# 5VBulkhead.net
KiCad netlist of a schematic drawn in Altium Designer
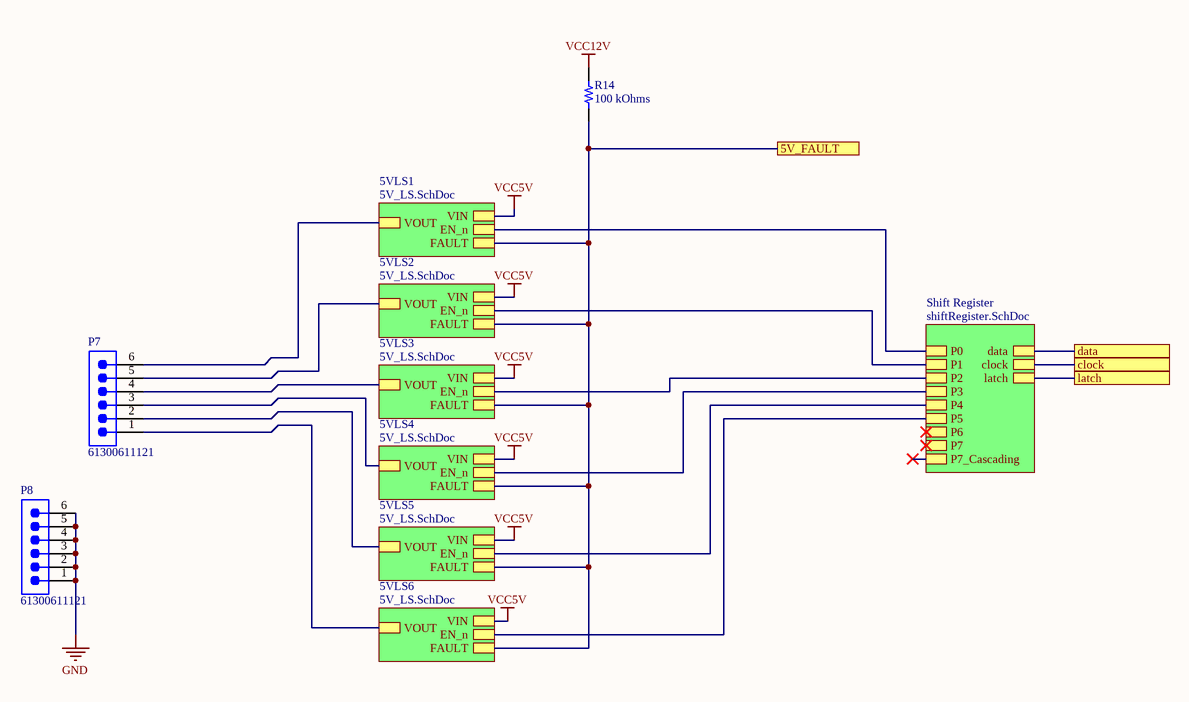
[diagram p0: 5VBulkhead.SchDoc]

(export (version "E")
  (design (tool "Eeschema 10.0.6"))
  (components
    (comp (ref "P7")
      (value "61300611121")
      (footprint "61300611121")
      (libsource (lib "Altium Content Vault") (part "Header_Male_1R_06P"))
    )
    (comp (ref "P8")
      (value "61300611121")
      (footprint "61300611121")
      (libsource (lib "Altium Content Vault") (part "Header_Male_1R_06P"))
    )
    (comp (ref "R14")
      (value "100 kOhms")
      (footprint "RES 0603_1608")
      (description "RES 100K OHM 0.1% 1/16W 0603")
      (fields
        (field (name "PART NUMBER") "RNCS0603BKE100K")
        (field (name "MANUFACTURER") "Stackpole Electronics Inc")
      )
      (libsource (lib "Celestial Altium Library - altium_library") (part "Resistor"))
    )
  )
  (nets
    (net (code "1") (name "/5V_FAULT") (class "Default")
      (node (ref "R14") (pin "1") (pinfunction "1_1") (pintype "passive"))
    )
    (net (code "11") (name "/VOUT") (class "Default")
      (node (ref "P7") (pin "6") (pinfunction "6_6") (pintype "passive"))
    )
    (net (code "12") (name "/VOUT_1") (class "Default")
      (node (ref "P7") (pin "5") (pinfunction "5_5") (pintype "passive"))
    )
    (net (code "13") (name "/VOUT_2") (class "Default")
      (node (ref "P7") (pin "4") (pinfunction "4_4") (pintype "passive"))
    )
    (net (code "14") (name "/VOUT_3") (class "Default")
      (node (ref "P7") (pin "3") (pinfunction "3_3") (pintype "passive"))
    )
    (net (code "15") (name "/VOUT_4") (class "Default")
      (node (ref "P7") (pin "2") (pinfunction "2_2") (pintype "passive"))
    )
    (net (code "16") (name "/VOUT_5") (class "Default")
      (node (ref "P7") (pin "1") (pinfunction "1_1") (pintype "passive"))
    )
    (net (code "20") (name "GND") (class "Default")
      (node (ref "P8") (pin "1") (pinfunction "1_1") (pintype "passive"))
      (node (ref "P8") (pin "2") (pinfunction "2_2") (pintype "passive"))
      (node (ref "P8") (pin "3") (pinfunction "3_3") (pintype "passive"))
      (node (ref "P8") (pin "4") (pinfunction "4_4") (pintype "passive"))
      (node (ref "P8") (pin "5") (pinfunction "5_5") (pintype "passive"))
      (node (ref "P8") (pin "6") (pinfunction "6_6") (pintype "passive"))
    )
    (net (code "22") (name "VCC12V") (class "Default")
      (node (ref "R14") (pin "2") (pinfunction "2_2") (pintype "passive"))
    )
  )
)
